# MucDuino_Banana.net
KiCad netlist of a schematic drawn in EAGLE
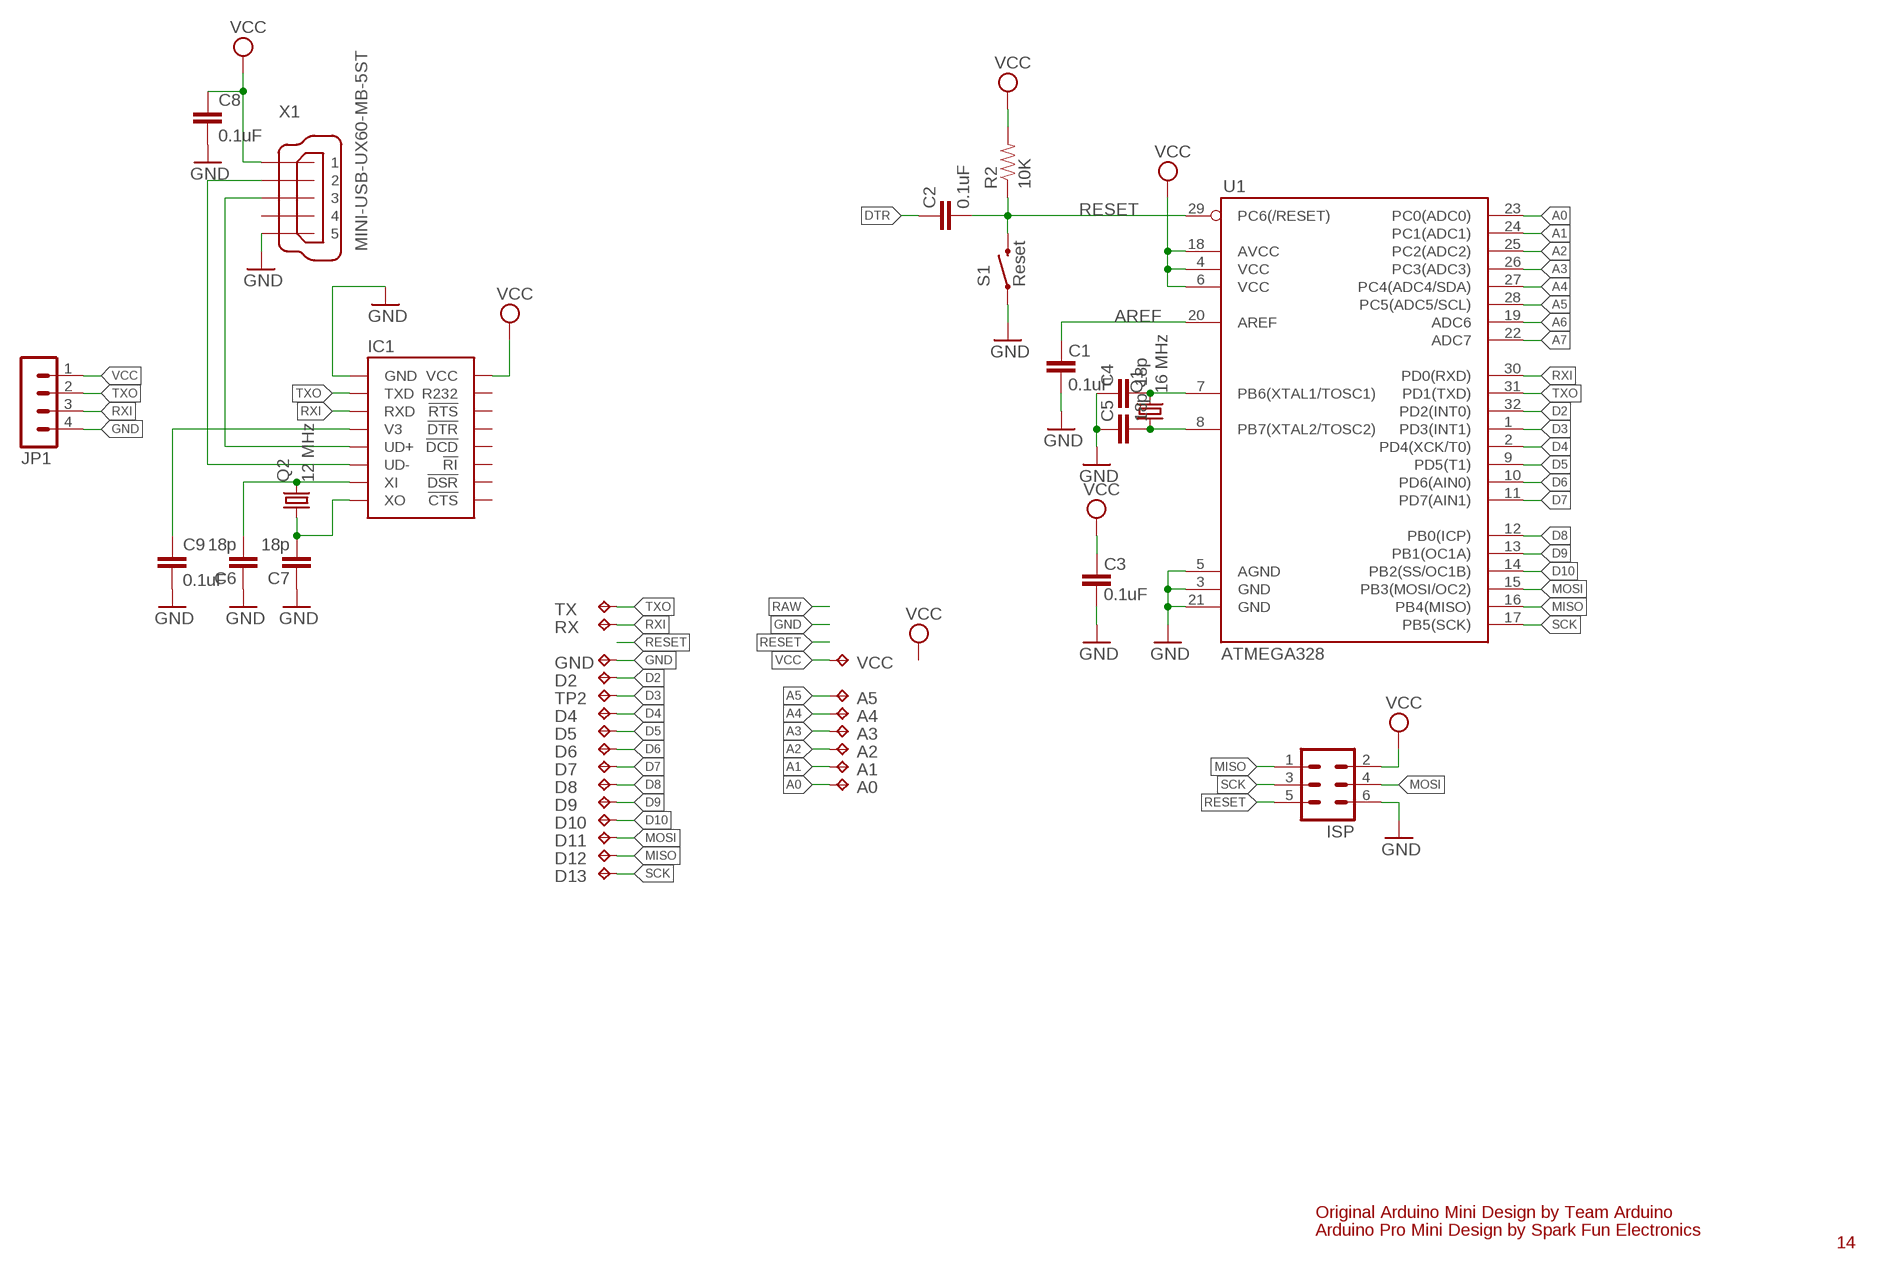
[diagram p0: schematic, sheet 1]

(export (version "E")
  (design (tool "Eeschema 10.0.6"))
  (components
    (comp (ref "A0")
      (value "TPPAD1-13")
      (footprint "eagle-import:P1-13")
      (libsource (lib "eagle-import") (part "TPPAD1-13"))
    )
    (comp (ref "A1")
      (value "TPPAD1-13")
      (footprint "eagle-import:P1-13")
      (libsource (lib "eagle-import") (part "TPPAD1-13"))
    )
    (comp (ref "A2")
      (value "TPPAD1-13")
      (footprint "eagle-import:P1-13")
      (libsource (lib "eagle-import") (part "TPPAD1-13"))
    )
    (comp (ref "A3")
      (value "TPPAD1-13")
      (footprint "eagle-import:P1-13")
      (libsource (lib "eagle-import") (part "TPPAD1-13"))
    )
    (comp (ref "A4")
      (value "TPPAD1-13")
      (footprint "eagle-import:P1-13")
      (libsource (lib "eagle-import") (part "TPPAD1-13"))
    )
    (comp (ref "A5")
      (value "TPPAD1-13")
      (footprint "eagle-import:P1-13")
      (libsource (lib "eagle-import") (part "TPPAD1-13"))
    )
    (comp (ref "C1")
      (value "0.1uF")
      (footprint "eagle-import:0603-CAP")
      (libsource (lib "eagle-import") (part "CAP0603-CAP"))
    )
    (comp (ref "C2")
      (value "0.1uF")
      (footprint "eagle-import:0603-CAP")
      (libsource (lib "eagle-import") (part "CAP0603-CAP"))
    )
    (comp (ref "C3")
      (value "0.1uF")
      (footprint "eagle-import:0603-CAP")
      (libsource (lib "eagle-import") (part "CAP0603-CAP"))
    )
    (comp (ref "C4")
      (value "18p")
      (footprint "eagle-import:0603-CAP")
      (libsource (lib "eagle-import") (part "CAP0603-CAP"))
    )
    (comp (ref "C5")
      (value "18p")
      (footprint "eagle-import:0603-CAP")
      (libsource (lib "eagle-import") (part "CAP0603-CAP"))
    )
    (comp (ref "C6")
      (value "18p")
      (footprint "eagle-import:0603-CAP")
      (libsource (lib "eagle-import") (part "CAP0603-CAP"))
    )
    (comp (ref "C7")
      (value "18p")
      (footprint "eagle-import:0603-CAP")
      (libsource (lib "eagle-import") (part "CAP0603-CAP"))
    )
    (comp (ref "C8")
      (value "0.1uF")
      (footprint "eagle-import:0603-CAP")
      (libsource (lib "eagle-import") (part "CAP0603-CAP"))
    )
    (comp (ref "C9")
      (value "0.1uF")
      (footprint "eagle-import:0603-CAP")
      (libsource (lib "eagle-import") (part "CAP0603-CAP"))
    )
    (comp (ref "D2")
      (value "TPPAD1-13")
      (footprint "eagle-import:P1-13")
      (libsource (lib "eagle-import") (part "TPPAD1-13"))
    )
    (comp (ref "D4")
      (value "TPPAD1-13")
      (footprint "eagle-import:P1-13")
      (libsource (lib "eagle-import") (part "TPPAD1-13"))
    )
    (comp (ref "D5")
      (value "TPPAD1-13")
      (footprint "eagle-import:P1-13")
      (libsource (lib "eagle-import") (part "TPPAD1-13"))
    )
    (comp (ref "D6")
      (value "TPPAD1-13")
      (footprint "eagle-import:P1-13")
      (libsource (lib "eagle-import") (part "TPPAD1-13"))
    )
    (comp (ref "D7")
      (value "TPPAD1-13")
      (footprint "eagle-import:P1-13")
      (libsource (lib "eagle-import") (part "TPPAD1-13"))
    )
    (comp (ref "D8")
      (value "TPPAD1-13")
      (footprint "eagle-import:P1-13")
      (libsource (lib "eagle-import") (part "TPPAD1-13"))
    )
    (comp (ref "D9")
      (value "TPPAD1-13")
      (footprint "eagle-import:P1-13")
      (libsource (lib "eagle-import") (part "TPPAD1-13"))
    )
    (comp (ref "D10")
      (value "TPPAD1-13")
      (footprint "eagle-import:P1-13")
      (libsource (lib "eagle-import") (part "TPPAD1-13"))
    )
    (comp (ref "D11")
      (value "TPPAD1-13")
      (footprint "eagle-import:P1-13")
      (libsource (lib "eagle-import") (part "TPPAD1-13"))
    )
    (comp (ref "D12")
      (value "TPPAD1-13")
      (footprint "eagle-import:P1-13")
      (libsource (lib "eagle-import") (part "TPPAD1-13"))
    )
    (comp (ref "D13")
      (value "TPPAD1-13")
      (footprint "eagle-import:P1-13")
      (libsource (lib "eagle-import") (part "TPPAD1-13"))
    )
    (comp (ref "GND")
      (value "TPPAD1-13")
      (footprint "eagle-import:P1-13")
      (libsource (lib "eagle-import") (part "TPPAD1-13"))
    )
    (comp (ref "IC1")
      (value "CH340G")
      (footprint "eagle-import:SOP16-209MM")
      (libsource (lib "eagle-import") (part "CH340G"))
    )
    (comp (ref "ISP")
      (value "MA03-2")
      (footprint "eagle-import:MA03-2")
      (libsource (lib "eagle-import") (part "MA03-2"))
    )
    (comp (ref "JP1")
      (value "MA04-1")
      (footprint "eagle-import:MA04-1")
      (libsource (lib "eagle-import") (part "MA04-1"))
    )
    (comp (ref "Q1")
      (value "16 MHz")
      (footprint "eagle-import:HC49UP")
      (libsource (lib "eagle-import") (part "CRYSTALHC49UP"))
    )
    (comp (ref "Q2")
      (value "12 MHz")
      (footprint "eagle-import:HC49UP")
      (libsource (lib "eagle-import") (part "CRYSTALHC49UP"))
    )
    (comp (ref "R2")
      (value "10K")
      (footprint "eagle-import:0603-RES")
      (libsource (lib "eagle-import") (part "RESISTOR0603-RES"))
    )
    (comp (ref "RX")
      (value "TPPAD1-13")
      (footprint "eagle-import:P1-13")
      (libsource (lib "eagle-import") (part "TPPAD1-13"))
    )
    (comp (ref "S1")
      (value "Reset")
      (footprint "eagle-import:TACTILE-SWITCH-SMD-ALT01")
      (libsource (lib "eagle-import") (part "SWITCH-MOMENTARY-2SMD-ALT01"))
    )
    (comp (ref "TP2")
      (value "TPPAD1-13")
      (footprint "eagle-import:P1-13")
      (libsource (lib "eagle-import") (part "TPPAD1-13"))
    )
    (comp (ref "TX")
      (value "TPPAD1-13")
      (footprint "eagle-import:P1-13")
      (libsource (lib "eagle-import") (part "TPPAD1-13"))
    )
    (comp (ref "U1")
      (value "ATMEGA328")
      (footprint "eagle-import:TQFP32-08")
      (libsource (lib "eagle-import") (part "ATMEGA168"))
    )
    (comp (ref "VCC")
      (value "TPPAD1-13")
      (footprint "eagle-import:P1-13")
      (libsource (lib "eagle-import") (part "TPPAD1-13"))
    )
    (comp (ref "X1")
      (value "MINI-USB-UX60-MB-5ST")
      (footprint "eagle-import:UX60-MB-5ST")
      (libsource (lib "eagle-import") (part "MINI-USB-UX60-MB-5ST"))
    )
  )
  (nets
    (net (code "1") (name "/AREF") (class "Default")
      (node (ref "C1") (pin "2") (pinfunction "2_2") (pintype "passive"))
      (node (ref "U1") (pin "20") (pinfunction "AREF_20") (pintype "bidirectional"))
    )
    (net (code "2") (name "A0") (class "Default")
      (node (ref "A0") (pin "TP") (pinfunction "TP_TP") (pintype "input"))
      (node (ref "U1") (pin "23") (pinfunction "PC0(ADC0)_23") (pintype "bidirectional"))
    )
    (net (code "3") (name "A1") (class "Default")
      (node (ref "A1") (pin "TP") (pinfunction "TP_TP") (pintype "input"))
      (node (ref "U1") (pin "24") (pinfunction "PC1(ADC1)_24") (pintype "bidirectional"))
    )
    (net (code "4") (name "A2") (class "Default")
      (node (ref "A2") (pin "TP") (pinfunction "TP_TP") (pintype "input"))
      (node (ref "U1") (pin "25") (pinfunction "PC2(ADC2)_25") (pintype "bidirectional"))
    )
    (net (code "5") (name "A3") (class "Default")
      (node (ref "A3") (pin "TP") (pinfunction "TP_TP") (pintype "input"))
      (node (ref "U1") (pin "26") (pinfunction "PC3(ADC3)_26") (pintype "bidirectional"))
    )
    (net (code "6") (name "A4") (class "Default")
      (node (ref "A4") (pin "TP") (pinfunction "TP_TP") (pintype "input"))
      (node (ref "U1") (pin "27") (pinfunction "PC4(ADC4/SDA)_27") (pintype "bidirectional"))
    )
    (net (code "7") (name "A5") (class "Default")
      (node (ref "A5") (pin "TP") (pinfunction "TP_TP") (pintype "input"))
      (node (ref "U1") (pin "28") (pinfunction "PC5(ADC5/SCL)_28") (pintype "bidirectional"))
    )
    (net (code "8") (name "A6") (class "Default")
      (node (ref "U1") (pin "19") (pinfunction "ADC6_19") (pintype "bidirectional"))
    )
    (net (code "9") (name "A7") (class "Default")
      (node (ref "U1") (pin "22") (pinfunction "ADC7_22") (pintype "bidirectional"))
    )
    (net (code "10") (name "D2") (class "Default")
      (node (ref "D2") (pin "TP") (pinfunction "TP_TP") (pintype "input"))
      (node (ref "U1") (pin "32") (pinfunction "PD2(INT0)_32") (pintype "bidirectional"))
    )
    (net (code "11") (name "D3") (class "Default")
      (node (ref "TP2") (pin "TP") (pinfunction "TP_TP") (pintype "input"))
      (node (ref "U1") (pin "1") (pinfunction "PD3(INT1)_1") (pintype "bidirectional"))
    )
    (net (code "12") (name "D4") (class "Default")
      (node (ref "D4") (pin "TP") (pinfunction "TP_TP") (pintype "input"))
      (node (ref "U1") (pin "2") (pinfunction "PD4(XCK/T0)_2") (pintype "bidirectional"))
    )
    (net (code "13") (name "D5") (class "Default")
      (node (ref "D5") (pin "TP") (pinfunction "TP_TP") (pintype "input"))
      (node (ref "U1") (pin "9") (pinfunction "PD5(T1)_9") (pintype "bidirectional"))
    )
    (net (code "14") (name "D6") (class "Default")
      (node (ref "D6") (pin "TP") (pinfunction "TP_TP") (pintype "input"))
      (node (ref "U1") (pin "10") (pinfunction "PD6(AIN0)_10") (pintype "bidirectional"))
    )
    (net (code "15") (name "D7") (class "Default")
      (node (ref "D7") (pin "TP") (pinfunction "TP_TP") (pintype "input"))
      (node (ref "U1") (pin "11") (pinfunction "PD7(AIN1)_11") (pintype "bidirectional"))
    )
    (net (code "16") (name "D8") (class "Default")
      (node (ref "D8") (pin "TP") (pinfunction "TP_TP") (pintype "input"))
      (node (ref "U1") (pin "12") (pinfunction "PB0(ICP)_12") (pintype "bidirectional"))
    )
    (net (code "17") (name "D9") (class "Default")
      (node (ref "D9") (pin "TP") (pinfunction "TP_TP") (pintype "input"))
      (node (ref "U1") (pin "13") (pinfunction "PB1(OC1A)_13") (pintype "bidirectional"))
    )
    (net (code "18") (name "D10") (class "Default")
      (node (ref "D10") (pin "TP") (pinfunction "TP_TP") (pintype "input"))
      (node (ref "U1") (pin "14") (pinfunction "PB2(SS/OC1B)_14") (pintype "bidirectional"))
    )
    (net (code "19") (name "DTR") (class "Default")
      (node (ref "C2") (pin "2") (pinfunction "2_2") (pintype "passive"))
    )
    (net (code "20") (name "GND") (class "Default")
      (node (ref "C1") (pin "1") (pinfunction "1_1") (pintype "passive"))
      (node (ref "C3") (pin "1") (pinfunction "1_1") (pintype "passive"))
      (node (ref "C4") (pin "2") (pinfunction "2_2") (pintype "passive"))
      (node (ref "C5") (pin "2") (pinfunction "2_2") (pintype "passive"))
      (node (ref "C6") (pin "2") (pinfunction "2_2") (pintype "passive"))
      (node (ref "C7") (pin "2") (pinfunction "2_2") (pintype "passive"))
      (node (ref "C8") (pin "2") (pinfunction "2_2") (pintype "passive"))
      (node (ref "C9") (pin "2") (pinfunction "2_2") (pintype "passive"))
      (node (ref "GND") (pin "TP") (pinfunction "TP_TP") (pintype "input"))
      (node (ref "IC1") (pin "P$1") (pinfunction "GND_P$1") (pintype "bidirectional"))
      (node (ref "ISP") (pin "6") (pinfunction "6_6") (pintype "passive"))
      (node (ref "JP1") (pin "4") (pinfunction "4_4") (pintype "passive"))
      (node (ref "S1") (pin "1") (pinfunction "1_1") (pintype "passive"))
      (node (ref "S1") (pin "2") (pinfunction "1_2") (pintype "passive"))
      (node (ref "U1") (pin "21") (pinfunction "GND_21") (pintype "bidirectional"))
      (node (ref "U1") (pin "3") (pinfunction "GND_3") (pintype "bidirectional"))
      (node (ref "U1") (pin "5") (pinfunction "AGND_5") (pintype "bidirectional"))
      (node (ref "X1") (pin "5") (pinfunction "5_5") (pintype "input"))
    )
    (net (code "21") (name "MISO") (class "Default")
      (node (ref "D12") (pin "TP") (pinfunction "TP_TP") (pintype "input"))
      (node (ref "ISP") (pin "1") (pinfunction "1_1") (pintype "passive"))
      (node (ref "U1") (pin "16") (pinfunction "PB4(MISO)_16") (pintype "bidirectional"))
    )
    (net (code "22") (name "MOSI") (class "Default")
      (node (ref "D11") (pin "TP") (pinfunction "TP_TP") (pintype "input"))
      (node (ref "ISP") (pin "4") (pinfunction "4_4") (pintype "passive"))
      (node (ref "U1") (pin "15") (pinfunction "PB3(MOSI/OC2)_15") (pintype "bidirectional"))
    )
    (net (code "23") (name "Net-(IC1-UD+)") (class "Default")
      (node (ref "IC1") (pin "P$5") (pinfunction "UD+_P$5") (pintype "bidirectional"))
      (node (ref "X1") (pin "3") (pinfunction "3_3") (pintype "input"))
    )
    (net (code "24") (name "Net-(IC1-UD-)") (class "Default")
      (node (ref "IC1") (pin "P$6") (pinfunction "UD-_P$6") (pintype "bidirectional"))
      (node (ref "X1") (pin "2") (pinfunction "2_2") (pintype "input"))
    )
    (net (code "25") (name "Net-(IC1-V3)") (class "Default")
      (node (ref "C9") (pin "1") (pinfunction "1_1") (pintype "passive"))
      (node (ref "IC1") (pin "P$4") (pinfunction "V3_P$4") (pintype "bidirectional"))
    )
    (net (code "26") (name "Net-(IC1-XI)") (class "Default")
      (node (ref "C6") (pin "1") (pinfunction "1_1") (pintype "passive"))
      (node (ref "IC1") (pin "P$7") (pinfunction "XI_P$7") (pintype "bidirectional"))
      (node (ref "Q2") (pin "2") (pinfunction "2_2") (pintype "passive"))
    )
    (net (code "27") (name "Net-(IC1-XO)") (class "Default")
      (node (ref "C7") (pin "1") (pinfunction "1_1") (pintype "passive"))
      (node (ref "IC1") (pin "P$8") (pinfunction "XO_P$8") (pintype "bidirectional"))
      (node (ref "Q2") (pin "1") (pinfunction "1_1") (pintype "passive"))
    )
    (net (code "28") (name "Net-(U1-PB6(XTAL1{slash}TOSC1))") (class "Default")
      (node (ref "C4") (pin "1") (pinfunction "1_1") (pintype "passive"))
      (node (ref "Q1") (pin "2") (pinfunction "2_2") (pintype "passive"))
      (node (ref "U1") (pin "7") (pinfunction "PB6(XTAL1/TOSC1)_7") (pintype "bidirectional"))
    )
    (net (code "29") (name "Net-(U1-PB7(XTAL2{slash}TOSC2))") (class "Default")
      (node (ref "C5") (pin "1") (pinfunction "1_1") (pintype "passive"))
      (node (ref "Q1") (pin "1") (pinfunction "1_1") (pintype "passive"))
      (node (ref "U1") (pin "8") (pinfunction "PB7(XTAL2/TOSC2)_8") (pintype "bidirectional"))
    )
    (net (code "31") (name "RESET") (class "Default")
      (node (ref "C2") (pin "1") (pinfunction "1_1") (pintype "passive"))
      (node (ref "ISP") (pin "5") (pinfunction "5_5") (pintype "passive"))
      (node (ref "R2") (pin "1") (pinfunction "1_1") (pintype "passive"))
      (node (ref "S1") (pin "3") (pinfunction "2_3") (pintype "passive"))
      (node (ref "S1") (pin "4") (pinfunction "2_4") (pintype "passive"))
      (node (ref "U1") (pin "29") (pinfunction "PC6(/RESET)_29") (pintype "bidirectional"))
    )
    (net (code "32") (name "RXI") (class "Default")
      (node (ref "IC1") (pin "P$3") (pinfunction "RXD_P$3") (pintype "bidirectional"))
      (node (ref "JP1") (pin "3") (pinfunction "3_3") (pintype "passive"))
      (node (ref "RX") (pin "TP") (pinfunction "TP_TP") (pintype "input"))
      (node (ref "U1") (pin "30") (pinfunction "PD0(RXD)_30") (pintype "bidirectional"))
    )
    (net (code "33") (name "SCK") (class "Default")
      (node (ref "D13") (pin "TP") (pinfunction "TP_TP") (pintype "input"))
      (node (ref "ISP") (pin "3") (pinfunction "3_3") (pintype "passive"))
      (node (ref "U1") (pin "17") (pinfunction "PB5(SCK)_17") (pintype "bidirectional"))
    )
    (net (code "34") (name "TXO") (class "Default")
      (node (ref "IC1") (pin "P$2") (pinfunction "TXD_P$2") (pintype "bidirectional"))
      (node (ref "JP1") (pin "2") (pinfunction "2_2") (pintype "passive"))
      (node (ref "TX") (pin "TP") (pinfunction "TP_TP") (pintype "input"))
      (node (ref "U1") (pin "31") (pinfunction "PD1(TXD)_31") (pintype "bidirectional"))
    )
    (net (code "35") (name "VCC") (class "Default")
      (node (ref "C3") (pin "2") (pinfunction "2_2") (pintype "passive"))
      (node (ref "C8") (pin "1") (pinfunction "1_1") (pintype "passive"))
      (node (ref "IC1") (pin "P$16") (pinfunction "VCC_P$16") (pintype "bidirectional"))
      (node (ref "ISP") (pin "2") (pinfunction "2_2") (pintype "passive"))
      (node (ref "JP1") (pin "1") (pinfunction "1_1") (pintype "passive"))
      (node (ref "R2") (pin "2") (pinfunction "2_2") (pintype "passive"))
      (node (ref "U1") (pin "18") (pinfunction "AVCC_18") (pintype "bidirectional"))
      (node (ref "U1") (pin "4") (pinfunction "VCC_4") (pintype "bidirectional"))
      (node (ref "U1") (pin "6") (pinfunction "VCC_6") (pintype "bidirectional"))
      (node (ref "VCC") (pin "TP") (pinfunction "TP_TP") (pintype "input"))
      (node (ref "X1") (pin "1") (pinfunction "1_1") (pintype "input"))
    )
    (net (code "36") (name "unconnected-(IC1-R232-PadP$15)") (class "Default")
      (node (ref "IC1") (pin "P$15") (pinfunction "R232_P$15") (pintype "bidirectional"))
    )
    (net (code "37") (name "unconnected-(IC1-~{CTS}-PadP$9)") (class "Default")
      (node (ref "IC1") (pin "P$9") (pinfunction "~{CTS}_P$9") (pintype "bidirectional"))
    )
    (net (code "38") (name "unconnected-(IC1-~{DCD}-PadP$12)") (class "Default")
      (node (ref "IC1") (pin "P$12") (pinfunction "~{DCD}_P$12") (pintype "bidirectional"))
    )
    (net (code "39") (name "unconnected-(IC1-~{DSR}-PadP$10)") (class "Default")
      (node (ref "IC1") (pin "P$10") (pinfunction "~{DSR}_P$10") (pintype "bidirectional"))
    )
    (net (code "40") (name "unconnected-(IC1-~{DTR}-PadP$13)") (class "Default")
      (node (ref "IC1") (pin "P$13") (pinfunction "~{DTR}_P$13") (pintype "bidirectional"))
    )
    (net (code "41") (name "unconnected-(IC1-~{RI}-PadP$11)") (class "Default")
      (node (ref "IC1") (pin "P$11") (pinfunction "~{RI}_P$11") (pintype "bidirectional"))
    )
    (net (code "42") (name "unconnected-(IC1-~{RTS}-PadP$14)") (class "Default")
      (node (ref "IC1") (pin "P$14") (pinfunction "~{RTS}_P$14") (pintype "bidirectional"))
    )
    (net (code "43") (name "unconnected-(X1-Pad4)") (class "Default")
      (node (ref "X1") (pin "4") (pinfunction "4_4") (pintype "input"))
    )
  )
)
